# VFD-Converter.net
KiCad netlist of a schematic drawn in EAGLE
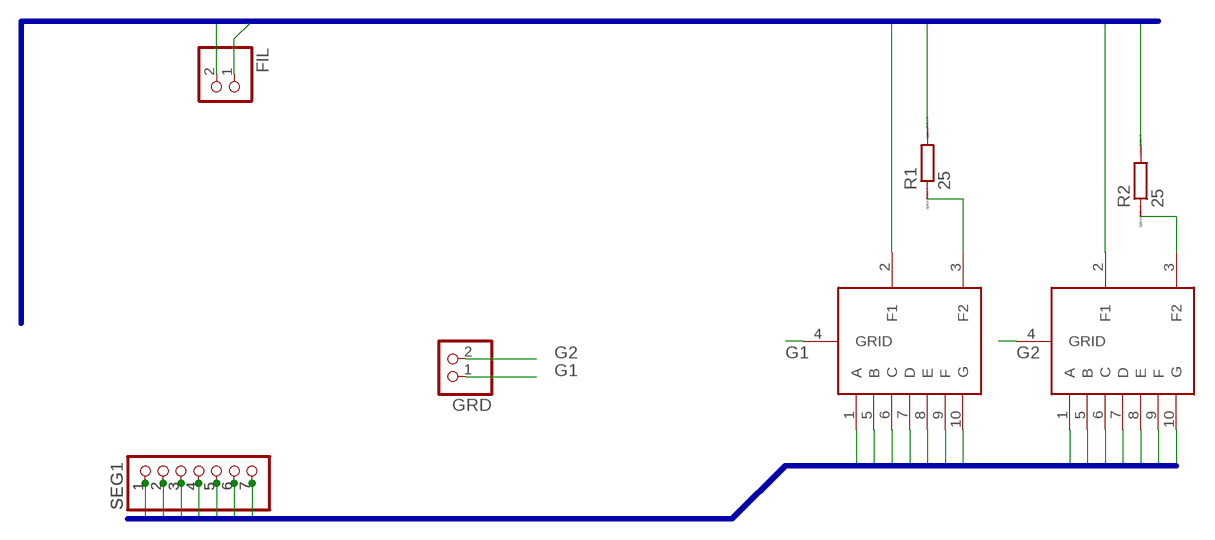
[diagram p0: schematic, sheet 1]

(export (version "E")
  (design (tool "Eeschema 10.0.6"))
  (components
    (comp (ref "FIL")
      (value "PINHD-1X2")
      (footprint "eagle-import:1X02")
      (libsource (lib "eagle-import") (part "PINHD-1X2"))
    )
    (comp (ref "GRD")
      (value "PINHD-1X2")
      (footprint "eagle-import:1X02")
      (libsource (lib "eagle-import") (part "PINHD-1X2"))
    )
    (comp (ref "R1")
      (value "25")
      (footprint "eagle-import:M0805")
      (libsource (lib "eagle-import") (part "R-EU_M0805"))
    )
    (comp (ref "R2")
      (value "25")
      (footprint "eagle-import:M0805")
      (libsource (lib "eagle-import") (part "R-EU_M0805"))
    )
    (comp (ref "SEG")
      (value "PINHD-1X7")
      (footprint "eagle-import:1X07")
      (libsource (lib "eagle-import") (part "PINHD-1X7"))
    )
    (comp (ref "SEG1")
      (value "PINHD-1X7")
      (footprint "eagle-import:1X07")
      (libsource (lib "eagle-import") (part "PINHD-1X7"))
    )
    (comp (ref "U$5")
      (value "IV-12")
      (footprint "eagle-import:NIXIE-11")
      (libsource (lib "eagle-import") (part "IV-12"))
    )
    (comp (ref "U$6")
      (value "IV-12")
      (footprint "eagle-import:NIXIE-11")
      (libsource (lib "eagle-import") (part "IV-12"))
    )
  )
  (nets
    (net (code "1") (name "/F1") (class "Default")
      (node (ref "FIL") (pin "1") (pinfunction "1_1") (pintype "passive"))
      (node (ref "U$5") (pin "2") (pinfunction "F1_2") (pintype "bidirectional"))
      (node (ref "U$6") (pin "2") (pinfunction "F1_2") (pintype "bidirectional"))
    )
    (net (code "2") (name "/F2") (class "Default")
      (node (ref "FIL") (pin "2") (pinfunction "2_2") (pintype "passive"))
      (node (ref "R1") (pin "2") (pinfunction "2_2") (pintype "passive"))
      (node (ref "R2") (pin "2") (pinfunction "2_2") (pintype "passive"))
    )
    (net (code "3") (name "/G1") (class "Default")
      (node (ref "GRD") (pin "1") (pinfunction "1_1") (pintype "passive"))
      (node (ref "U$5") (pin "4") (pinfunction "GRID_4") (pintype "bidirectional"))
    )
    (net (code "4") (name "/G2") (class "Default")
      (node (ref "GRD") (pin "2") (pinfunction "2_2") (pintype "passive"))
      (node (ref "U$6") (pin "4") (pinfunction "GRID_4") (pintype "bidirectional"))
    )
    (net (code "5") (name "/SEG1") (class "Default")
      (node (ref "SEG") (pin "1") (pinfunction "1_1") (pintype "passive"))
      (node (ref "SEG1") (pin "1") (pinfunction "1_1") (pintype "passive"))
      (node (ref "U$5") (pin "1") (pinfunction "A_1") (pintype "bidirectional"))
      (node (ref "U$6") (pin "1") (pinfunction "A_1") (pintype "bidirectional"))
    )
    (net (code "6") (name "/SEG2") (class "Default")
      (node (ref "SEG") (pin "2") (pinfunction "2_2") (pintype "passive"))
      (node (ref "SEG1") (pin "2") (pinfunction "2_2") (pintype "passive"))
      (node (ref "U$5") (pin "5") (pinfunction "B_5") (pintype "bidirectional"))
      (node (ref "U$6") (pin "5") (pinfunction "B_5") (pintype "bidirectional"))
    )
    (net (code "7") (name "/SEG3") (class "Default")
      (node (ref "SEG") (pin "3") (pinfunction "3_3") (pintype "passive"))
      (node (ref "SEG1") (pin "3") (pinfunction "3_3") (pintype "passive"))
      (node (ref "U$5") (pin "6") (pinfunction "C_6") (pintype "bidirectional"))
      (node (ref "U$6") (pin "6") (pinfunction "C_6") (pintype "bidirectional"))
    )
    (net (code "8") (name "/SEG4") (class "Default")
      (node (ref "SEG") (pin "4") (pinfunction "4_4") (pintype "passive"))
      (node (ref "SEG1") (pin "4") (pinfunction "4_4") (pintype "passive"))
      (node (ref "U$5") (pin "7") (pinfunction "D_7") (pintype "bidirectional"))
      (node (ref "U$6") (pin "7") (pinfunction "D_7") (pintype "bidirectional"))
    )
    (net (code "9") (name "/SEG5") (class "Default")
      (node (ref "SEG") (pin "5") (pinfunction "5_5") (pintype "passive"))
      (node (ref "SEG1") (pin "5") (pinfunction "5_5") (pintype "passive"))
      (node (ref "U$5") (pin "8") (pinfunction "E_8") (pintype "bidirectional"))
      (node (ref "U$6") (pin "8") (pinfunction "E_8") (pintype "bidirectional"))
    )
    (net (code "10") (name "/SEG6") (class "Default")
      (node (ref "SEG") (pin "6") (pinfunction "6_6") (pintype "passive"))
      (node (ref "SEG1") (pin "6") (pinfunction "6_6") (pintype "passive"))
      (node (ref "U$5") (pin "9") (pinfunction "F_9") (pintype "bidirectional"))
      (node (ref "U$6") (pin "9") (pinfunction "F_9") (pintype "bidirectional"))
    )
    (net (code "11") (name "/SEG7") (class "Default")
      (node (ref "SEG") (pin "7") (pinfunction "7_7") (pintype "passive"))
      (node (ref "SEG1") (pin "7") (pinfunction "7_7") (pintype "passive"))
      (node (ref "U$5") (pin "10") (pinfunction "G_10") (pintype "bidirectional"))
      (node (ref "U$6") (pin "10") (pinfunction "G_10") (pintype "bidirectional"))
    )
    (net (code "12") (name "Net-(U$5-F2)") (class "Default")
      (node (ref "R1") (pin "1") (pinfunction "1_1") (pintype "passive"))
      (node (ref "U$5") (pin "3") (pinfunction "F2_3") (pintype "bidirectional"))
    )
    (net (code "13") (name "Net-(U$6-F2)") (class "Default")
      (node (ref "R2") (pin "1") (pinfunction "1_1") (pintype "passive"))
      (node (ref "U$6") (pin "3") (pinfunction "F2_3") (pintype "bidirectional"))
    )
  )
)
